# bikebadge.net
KiCad netlist of a schematic drawn in EAGLE
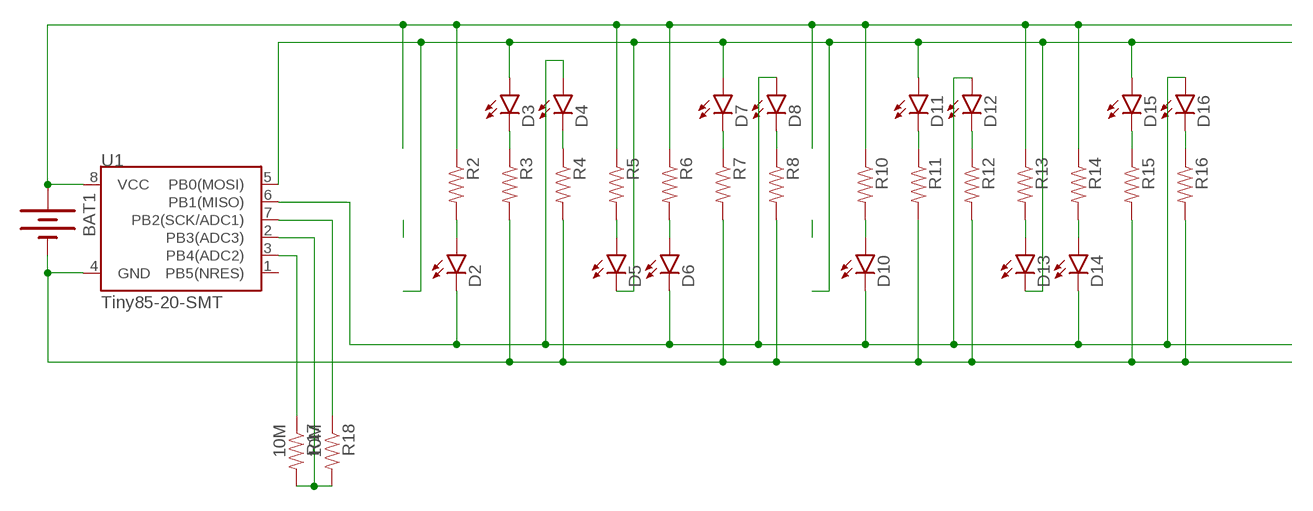
[diagram p0: schematic, sheet 1]

(export (version "E")
  (design (tool "Eeschema 10.0.6"))
  (components
    (comp (ref "BAT1")
      (value "BATTERY20PTH")
      (footprint "eagle-import:BATTCOM_20MM_PTH")
      (libsource (lib "eagle-import") (part "BATTERY20PTH"))
    )
    (comp (ref "D2")
      (value "LED")
      (footprint "eagle-import:LED-REV-MNT")
      (libsource (lib "eagle-import") (part "LED"))
    )
    (comp (ref "D3")
      (value "LED")
      (footprint "eagle-import:LED-REV-MNT")
      (libsource (lib "eagle-import") (part "LED"))
    )
    (comp (ref "D4")
      (value "LED")
      (footprint "eagle-import:LED-REV-MNT")
      (libsource (lib "eagle-import") (part "LED"))
    )
    (comp (ref "D5")
      (value "LED")
      (footprint "eagle-import:LED-REV-MNT")
      (libsource (lib "eagle-import") (part "LED"))
    )
    (comp (ref "D6")
      (value "LED")
      (footprint "eagle-import:LED-REV-MNT")
      (libsource (lib "eagle-import") (part "LED"))
    )
    (comp (ref "D7")
      (value "LED")
      (footprint "eagle-import:LED-REV-MNT")
      (libsource (lib "eagle-import") (part "LED"))
    )
    (comp (ref "D8")
      (value "LED")
      (footprint "eagle-import:LED-REV-MNT")
      (libsource (lib "eagle-import") (part "LED"))
    )
    (comp (ref "D10")
      (value "LED")
      (footprint "eagle-import:LED-REV-MNT")
      (libsource (lib "eagle-import") (part "LED"))
    )
    (comp (ref "D11")
      (value "LED")
      (footprint "eagle-import:LED-REV-MNT")
      (libsource (lib "eagle-import") (part "LED"))
    )
    (comp (ref "D12")
      (value "LED")
      (footprint "eagle-import:LED-REV-MNT")
      (libsource (lib "eagle-import") (part "LED"))
    )
    (comp (ref "D13")
      (value "LED")
      (footprint "eagle-import:LED-REV-MNT")
      (libsource (lib "eagle-import") (part "LED"))
    )
    (comp (ref "D14")
      (value "LED")
      (footprint "eagle-import:LED-REV-MNT")
      (libsource (lib "eagle-import") (part "LED"))
    )
    (comp (ref "D15")
      (value "LED")
      (footprint "eagle-import:LED-REV-MNT")
      (libsource (lib "eagle-import") (part "LED"))
    )
    (comp (ref "D16")
      (value "LED")
      (footprint "eagle-import:LED-REV-MNT")
      (libsource (lib "eagle-import") (part "LED"))
    )
    (comp (ref "R2")
      (value "RESISTOR1206")
      (footprint "eagle-import:1206")
      (libsource (lib "eagle-import") (part "RESISTOR1206"))
    )
    (comp (ref "R3")
      (value "RESISTOR1206")
      (footprint "eagle-import:1206")
      (libsource (lib "eagle-import") (part "RESISTOR1206"))
    )
    (comp (ref "R4")
      (value "RESISTOR1206")
      (footprint "eagle-import:1206")
      (libsource (lib "eagle-import") (part "RESISTOR1206"))
    )
    (comp (ref "R5")
      (value "RESISTOR1206")
      (footprint "eagle-import:1206")
      (libsource (lib "eagle-import") (part "RESISTOR1206"))
    )
    (comp (ref "R6")
      (value "RESISTOR1206")
      (footprint "eagle-import:1206")
      (libsource (lib "eagle-import") (part "RESISTOR1206"))
    )
    (comp (ref "R7")
      (value "RESISTOR1206")
      (footprint "eagle-import:1206")
      (libsource (lib "eagle-import") (part "RESISTOR1206"))
    )
    (comp (ref "R8")
      (value "RESISTOR1206")
      (footprint "eagle-import:1206")
      (libsource (lib "eagle-import") (part "RESISTOR1206"))
    )
    (comp (ref "R10")
      (value "RESISTOR1206")
      (footprint "eagle-import:1206")
      (libsource (lib "eagle-import") (part "RESISTOR1206"))
    )
    (comp (ref "R11")
      (value "RESISTOR1206")
      (footprint "eagle-import:1206")
      (libsource (lib "eagle-import") (part "RESISTOR1206"))
    )
    (comp (ref "R12")
      (value "RESISTOR1206")
      (footprint "eagle-import:1206")
      (libsource (lib "eagle-import") (part "RESISTOR1206"))
    )
    (comp (ref "R13")
      (value "RESISTOR1206")
      (footprint "eagle-import:1206")
      (libsource (lib "eagle-import") (part "RESISTOR1206"))
    )
    (comp (ref "R14")
      (value "RESISTOR1206")
      (footprint "eagle-import:1206")
      (libsource (lib "eagle-import") (part "RESISTOR1206"))
    )
    (comp (ref "R15")
      (value "RESISTOR1206")
      (footprint "eagle-import:1206")
      (libsource (lib "eagle-import") (part "RESISTOR1206"))
    )
    (comp (ref "R16")
      (value "RESISTOR1206")
      (footprint "eagle-import:1206")
      (libsource (lib "eagle-import") (part "RESISTOR1206"))
    )
    (comp (ref "R17")
      (value "10M")
      (footprint "eagle-import:0805")
      (libsource (lib "eagle-import") (part "RESISTOR0805-RES"))
    )
    (comp (ref "R18")
      (value "10M")
      (footprint "eagle-import:0805")
      (libsource (lib "eagle-import") (part "RESISTOR0805-RES"))
    )
    (comp (ref "U1")
      (value "Tiny85-20-SMT")
      (footprint "eagle-import:SO08-EIAJ")
      (libsource (lib "eagle-import") (part "ATTINY45TINY85-20-SMT"))
    )
  )
  (nets
    (net (code "1") (name "Net-(BAT1-+)") (class "Default")
      (node (ref "BAT1") (pin "1") (pinfunction "+_1") (pintype "power_in"))
      (node (ref "R10") (pin "1") (pinfunction "1_1") (pintype "passive"))
      (node (ref "R13") (pin "1") (pinfunction "1_1") (pintype "passive"))
      (node (ref "R14") (pin "1") (pinfunction "1_1") (pintype "passive"))
      (node (ref "R2") (pin "1") (pinfunction "1_1") (pintype "passive"))
      (node (ref "R5") (pin "1") (pinfunction "1_1") (pintype "passive"))
      (node (ref "R6") (pin "1") (pinfunction "1_1") (pintype "passive"))
      (node (ref "U1") (pin "8") (pinfunction "VCC_8") (pintype "bidirectional"))
    )
    (net (code "2") (name "Net-(BAT1--)") (class "Default")
      (node (ref "BAT1") (pin "2") (pinfunction "-_2") (pintype "power_in"))
      (node (ref "R11") (pin "2") (pinfunction "2_2") (pintype "passive"))
      (node (ref "R12") (pin "2") (pinfunction "2_2") (pintype "passive"))
      (node (ref "R15") (pin "2") (pinfunction "2_2") (pintype "passive"))
      (node (ref "R16") (pin "2") (pinfunction "2_2") (pintype "passive"))
      (node (ref "R3") (pin "2") (pinfunction "2_2") (pintype "passive"))
      (node (ref "R4") (pin "2") (pinfunction "2_2") (pintype "passive"))
      (node (ref "R7") (pin "2") (pinfunction "2_2") (pintype "passive"))
      (node (ref "R8") (pin "2") (pinfunction "2_2") (pintype "passive"))
      (node (ref "U1") (pin "4") (pinfunction "GND_4") (pintype "bidirectional"))
    )
    (net (code "3") (name "Net-(D2-PadA)") (class "Default")
      (node (ref "D2") (pin "A") (pinfunction "A_A") (pintype "passive"))
      (node (ref "R2") (pin "2") (pinfunction "2_2") (pintype "passive"))
    )
    (net (code "4") (name "Net-(D3-PadC)") (class "Default")
      (node (ref "D3") (pin "C") (pinfunction "C_C") (pintype "passive"))
      (node (ref "R3") (pin "1") (pinfunction "1_1") (pintype "passive"))
    )
    (net (code "5") (name "Net-(D4-PadC)") (class "Default")
      (node (ref "D4") (pin "C") (pinfunction "C_C") (pintype "passive"))
      (node (ref "R4") (pin "1") (pinfunction "1_1") (pintype "passive"))
    )
    (net (code "6") (name "Net-(D5-PadA)") (class "Default")
      (node (ref "D5") (pin "A") (pinfunction "A_A") (pintype "passive"))
      (node (ref "R5") (pin "2") (pinfunction "2_2") (pintype "passive"))
    )
    (net (code "7") (name "Net-(D6-PadA)") (class "Default")
      (node (ref "D6") (pin "A") (pinfunction "A_A") (pintype "passive"))
      (node (ref "R6") (pin "2") (pinfunction "2_2") (pintype "passive"))
    )
    (net (code "8") (name "Net-(D7-PadC)") (class "Default")
      (node (ref "D7") (pin "C") (pinfunction "C_C") (pintype "passive"))
      (node (ref "R7") (pin "1") (pinfunction "1_1") (pintype "passive"))
    )
    (net (code "9") (name "Net-(D8-PadC)") (class "Default")
      (node (ref "D8") (pin "C") (pinfunction "C_C") (pintype "passive"))
      (node (ref "R8") (pin "1") (pinfunction "1_1") (pintype "passive"))
    )
    (net (code "10") (name "Net-(D10-PadA)") (class "Default")
      (node (ref "D10") (pin "A") (pinfunction "A_A") (pintype "passive"))
      (node (ref "R10") (pin "2") (pinfunction "2_2") (pintype "passive"))
    )
    (net (code "11") (name "Net-(D11-PadC)") (class "Default")
      (node (ref "D11") (pin "C") (pinfunction "C_C") (pintype "passive"))
      (node (ref "R11") (pin "1") (pinfunction "1_1") (pintype "passive"))
    )
    (net (code "12") (name "Net-(D12-PadC)") (class "Default")
      (node (ref "D12") (pin "C") (pinfunction "C_C") (pintype "passive"))
      (node (ref "R12") (pin "1") (pinfunction "1_1") (pintype "passive"))
    )
    (net (code "13") (name "Net-(D13-PadA)") (class "Default")
      (node (ref "D13") (pin "A") (pinfunction "A_A") (pintype "passive"))
      (node (ref "R13") (pin "2") (pinfunction "2_2") (pintype "passive"))
    )
    (net (code "14") (name "Net-(D14-PadA)") (class "Default")
      (node (ref "D14") (pin "A") (pinfunction "A_A") (pintype "passive"))
      (node (ref "R14") (pin "2") (pinfunction "2_2") (pintype "passive"))
    )
    (net (code "15") (name "Net-(D15-PadC)") (class "Default")
      (node (ref "D15") (pin "C") (pinfunction "C_C") (pintype "passive"))
      (node (ref "R15") (pin "1") (pinfunction "1_1") (pintype "passive"))
    )
    (net (code "16") (name "Net-(D16-PadC)") (class "Default")
      (node (ref "D16") (pin "C") (pinfunction "C_C") (pintype "passive"))
      (node (ref "R16") (pin "1") (pinfunction "1_1") (pintype "passive"))
    )
    (net (code "17") (name "Net-(U1-PB0(MOSI))") (class "Default")
      (node (ref "D11") (pin "A") (pinfunction "A_A") (pintype "passive"))
      (node (ref "D13") (pin "C") (pinfunction "C_C") (pintype "passive"))
      (node (ref "D15") (pin "A") (pinfunction "A_A") (pintype "passive"))
      (node (ref "D3") (pin "A") (pinfunction "A_A") (pintype "passive"))
      (node (ref "D5") (pin "C") (pinfunction "C_C") (pintype "passive"))
      (node (ref "D7") (pin "A") (pinfunction "A_A") (pintype "passive"))
      (node (ref "U1") (pin "5") (pinfunction "PB0(MOSI)_5") (pintype "bidirectional"))
    )
    (net (code "18") (name "Net-(U1-PB1(MISO))") (class "Default")
      (node (ref "D10") (pin "C") (pinfunction "C_C") (pintype "passive"))
      (node (ref "D12") (pin "A") (pinfunction "A_A") (pintype "passive"))
      (node (ref "D14") (pin "C") (pinfunction "C_C") (pintype "passive"))
      (node (ref "D16") (pin "A") (pinfunction "A_A") (pintype "passive"))
      (node (ref "D2") (pin "C") (pinfunction "C_C") (pintype "passive"))
      (node (ref "D4") (pin "A") (pinfunction "A_A") (pintype "passive"))
      (node (ref "D6") (pin "C") (pinfunction "C_C") (pintype "passive"))
      (node (ref "D8") (pin "A") (pinfunction "A_A") (pintype "passive"))
      (node (ref "U1") (pin "6") (pinfunction "PB1(MISO)_6") (pintype "bidirectional"))
    )
    (net (code "19") (name "Net-(U1-PB2(SCK{slash}ADC1))") (class "Default")
      (node (ref "R18") (pin "1") (pinfunction "1_1") (pintype "passive"))
      (node (ref "U1") (pin "7") (pinfunction "PB2(SCK/ADC1)_7") (pintype "bidirectional"))
    )
    (net (code "20") (name "Net-(U1-PB3(ADC3))") (class "Default")
      (node (ref "R17") (pin "2") (pinfunction "2_2") (pintype "passive"))
      (node (ref "R18") (pin "2") (pinfunction "2_2") (pintype "passive"))
      (node (ref "U1") (pin "2") (pinfunction "PB3(ADC3)_2") (pintype "bidirectional"))
    )
    (net (code "21") (name "Net-(U1-PB4(ADC2))") (class "Default")
      (node (ref "R17") (pin "1") (pinfunction "1_1") (pintype "passive"))
      (node (ref "U1") (pin "3") (pinfunction "PB4(ADC2)_3") (pintype "bidirectional"))
    )
    (net (code "22") (name "unconnected-(U1-PB5(NRES)-Pad1)") (class "Default")
      (node (ref "U1") (pin "1") (pinfunction "PB5(NRES)_1") (pintype "bidirectional"))
    )
  )
)
